# postomatMainBoard_2021-04-18_15-55-46.net
KiCad netlist of a schematic drawn in EasyEDA
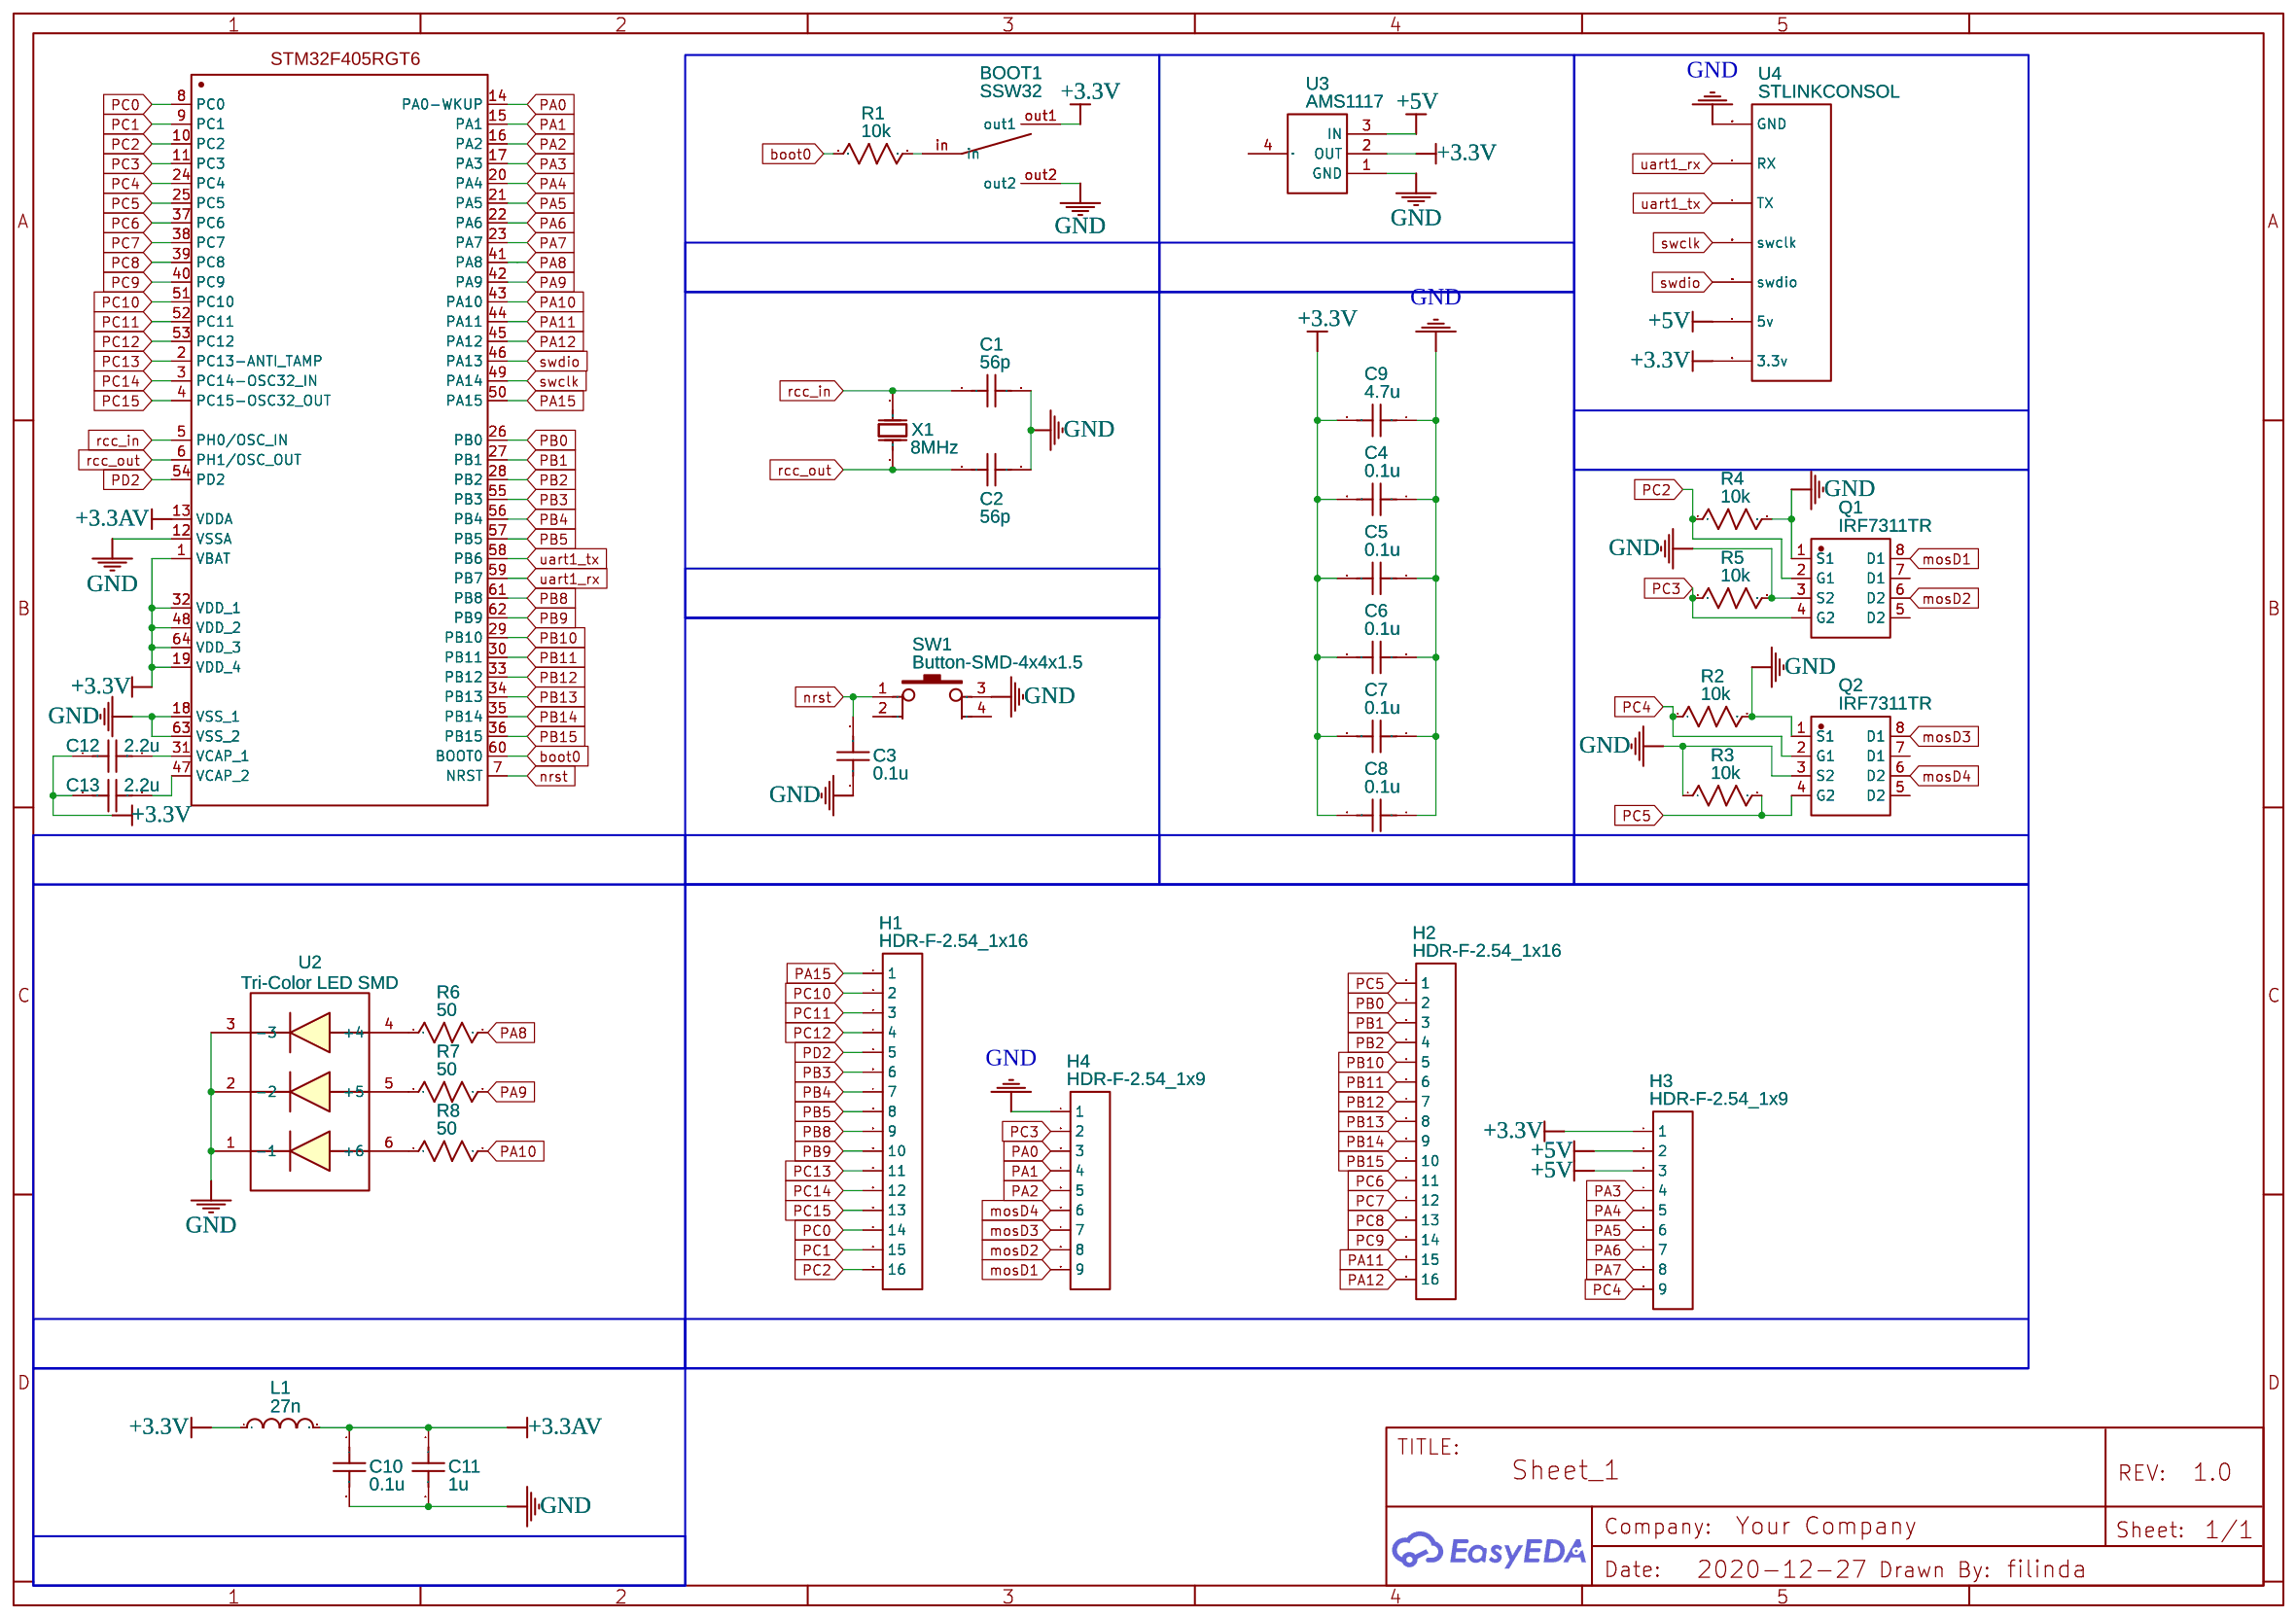
[diagram p0: schematic sheet]

(export (version "E")
  (design (tool "Eeschema 10.0.6"))
  (components
    (comp (ref "BOOT1") (value "SSW32") (libsource (lib "") (part "SSW32")))
    (comp (ref "C1") (value "56p") (libsource (lib "") (part "C_0805_US")))
    (comp (ref "C2") (value "56p") (libsource (lib "") (part "C_0805_US")))
    (comp (ref "C3") (value "0.1u") (libsource (lib "") (part "C_0603_US_3")))
    (comp (ref "C4") (value "0.1u") (libsource (lib "") (part "C_0603_US_1")))
    (comp (ref "C5") (value "0.1u") (libsource (lib "") (part "C_0603_US_1")))
    (comp (ref "C6") (value "0.1u") (libsource (lib "") (part "C_0603_US_1")))
    (comp (ref "C7") (value "0.1u") (libsource (lib "") (part "C_0603_US_1")))
    (comp (ref "C8") (value "0.1u") (libsource (lib "") (part "C_0603_US_1")))
    (comp (ref "C9") (value "4.7u") (libsource (lib "") (part "C_0603_US_1")))
    (comp (ref "C10") (value "0.1u") (libsource (lib "") (part "C_0603_US_2")))
    (comp (ref "C11") (value "1u") (libsource (lib "") (part "C_0603_US_2")))
    (comp (ref "C12") (value "2.2u") (libsource (lib "") (part "C_0603_US")))
    (comp (ref "C13") (value "2.2u") (libsource (lib "") (part "C_0603_US")))
    (comp (ref "H1")
      (value "HDR-F-2.54_1x16")
      (fields (field (name "BOM_Supplier Part") "C66987"))
      (libsource (lib "") (part "HDR-F-2.54_1x16"))
    )
    (comp (ref "H2")
      (value "HDR-F-2.54_1x16")
      (fields (field (name "BOM_Supplier Part") "C66987"))
      (libsource (lib "") (part "HDR-F-2.54_1x16"))
    )
    (comp (ref "H3")
      (value "HDR-F-2.54_1x9")
      (fields (field (name "BOM_Supplier Part") "C124417"))
      (libsource (lib "") (part "HDR-F-2.54_1x9"))
    )
    (comp (ref "H4")
      (value "HDR-F-2.54_1x9")
      (fields (field (name "BOM_Supplier Part") "C124417"))
      (libsource (lib "") (part "HDR-F-2.54_1x9"))
    )
    (comp (ref "L1") (value "27n") (libsource (lib "") (part "L0805_US")))
    (comp (ref "Q1")
      (value "IRF7311TR")
      (fields (field (name "BOM_Supplier Part") "C693288"))
      (libsource (lib "") (part "IRF7311TR"))
    )
    (comp (ref "Q2")
      (value "IRF7311TR")
      (fields (field (name "BOM_Supplier Part") "C693288"))
      (libsource (lib "") (part "IRF7311TR"))
    )
    (comp (ref "R1") (value "10k") (libsource (lib "") (part "R_1206_US")))
    (comp (ref "R2") (value "10k") (libsource (lib "") (part "R_1206_US")))
    (comp (ref "R3") (value "10k") (libsource (lib "") (part "R_1206_US")))
    (comp (ref "R4") (value "10k") (libsource (lib "") (part "R_1206_US")))
    (comp (ref "R5") (value "10k") (libsource (lib "") (part "R_1206_US")))
    (comp (ref "R6") (value "50") (libsource (lib "") (part "R_1206_US")))
    (comp (ref "R7") (value "50") (libsource (lib "") (part "R_1206_US")))
    (comp (ref "R8") (value "50") (libsource (lib "") (part "R_1206_US")))
    (comp (ref "SW1")
      (value "Button-SMD-4x4x1.5")
      (fields
        (field (name "BOM_Manufacturer Part") "4*4*1.5Copper head,260G, 0.25mm,")
        (field (name "BOM_Supplier Part") "C71830")
      )
      (libsource (lib "") (part "Button-SMD-4x4x1.5"))
    )
    (comp (ref "U1") (value "STM32F405RGT6") (libsource (lib "") (part "STM32F405RGT6")))
    (comp (ref "U2")
      (value "Tri-Color LED SMD")
      (fields
        (field (name "BOM_Manufacturer Part") "TO-5050BC-MRPBFGF")
        (field (name "BOM_Supplier Part") "A-4680")
      )
      (libsource (lib "") (part "Tri-Color LED SMD"))
    )
    (comp (ref "U3") (value "AMS1117") (libsource (lib "") (part "AMS1117")))
    (comp (ref "U4") (value "STLINKCONSOL") (libsource (lib "") (part "STLINKCONSOL")))
    (comp (ref "X1")
      (value "8MHz")
      (fields
        (field (name "BOM_Manufacturer Part") "HC-49SM8MHz20pF30ppm")
        (field (name "BOM_Supplier Part") "C107426")
      )
      (libsource (lib "") (part "HC-49SM8MHZ20PF30PPM"))
    )
  )
  (nets
    (net (code "1") (name "+3.3AV") (class "Default")
      (node (ref "C10") (pin "1") (pinfunction "1_1") (pintype "unspecified"))
      (node (ref "C11") (pin "1") (pinfunction "1_1") (pintype "unspecified"))
      (node (ref "L1") (pin "2") (pinfunction "2_2") (pintype "unspecified"))
      (node (ref "U1") (pin "13") (pinfunction "VDDA_13") (pintype "unspecified"))
    )
    (net (code "2") (name "+3.3V") (class "Default")
      (node (ref "BOOT1") (pin "out1") (pinfunction "out1_out1") (pintype "unspecified"))
      (node (ref "C12") (pin "1") (pinfunction "1_1") (pintype "unspecified"))
      (node (ref "C13") (pin "1") (pinfunction "1_1") (pintype "unspecified"))
      (node (ref "C4") (pin "2") (pinfunction "2_2") (pintype "unspecified"))
      (node (ref "C5") (pin "2") (pinfunction "2_2") (pintype "unspecified"))
      (node (ref "C6") (pin "2") (pinfunction "2_2") (pintype "unspecified"))
      (node (ref "C7") (pin "2") (pinfunction "2_2") (pintype "unspecified"))
      (node (ref "C8") (pin "2") (pinfunction "2_2") (pintype "unspecified"))
      (node (ref "C9") (pin "2") (pinfunction "2_2") (pintype "unspecified"))
      (node (ref "H3") (pin "1") (pinfunction "1_1") (pintype "unspecified"))
      (node (ref "L1") (pin "1") (pinfunction "1_1") (pintype "unspecified"))
      (node (ref "U1") (pin "1") (pinfunction "VBAT_1") (pintype "unspecified"))
      (node (ref "U1") (pin "19") (pinfunction "VDD_4_19") (pintype "unspecified"))
      (node (ref "U1") (pin "32") (pinfunction "VDD_1_32") (pintype "unspecified"))
      (node (ref "U1") (pin "48") (pinfunction "VDD_2_48") (pintype "unspecified"))
      (node (ref "U1") (pin "64") (pinfunction "VDD_3_64") (pintype "unspecified"))
      (node (ref "U3") (pin "2") (pinfunction "OUT_2") (pintype "unspecified"))
      (node (ref "U4") (pin "3.3v") (pinfunction "3.3v_3.3v") (pintype "unspecified"))
    )
    (net (code "3") (name "+5V") (class "Default")
      (node (ref "H3") (pin "2") (pinfunction "2_2") (pintype "unspecified"))
      (node (ref "H3") (pin "3") (pinfunction "3_3") (pintype "unspecified"))
      (node (ref "U3") (pin "3") (pinfunction "IN_3") (pintype "unspecified"))
      (node (ref "U4") (pin "5v") (pinfunction "5v_5v") (pintype "unspecified"))
    )
    (net (code "4") (name "GND") (class "Default")
      (node (ref "BOOT1") (pin "out2") (pinfunction "out2_out2") (pintype "unspecified"))
      (node (ref "C1") (pin "2") (pinfunction "2_2") (pintype "unspecified"))
      (node (ref "C10") (pin "2") (pinfunction "2_2") (pintype "unspecified"))
      (node (ref "C11") (pin "2") (pinfunction "2_2") (pintype "unspecified"))
      (node (ref "C2") (pin "2") (pinfunction "2_2") (pintype "unspecified"))
      (node (ref "C3") (pin "1") (pinfunction "1_1") (pintype "unspecified"))
      (node (ref "C4") (pin "1") (pinfunction "1_1") (pintype "unspecified"))
      (node (ref "C5") (pin "1") (pinfunction "1_1") (pintype "unspecified"))
      (node (ref "C6") (pin "1") (pinfunction "1_1") (pintype "unspecified"))
      (node (ref "C7") (pin "1") (pinfunction "1_1") (pintype "unspecified"))
      (node (ref "C8") (pin "1") (pinfunction "1_1") (pintype "unspecified"))
      (node (ref "C9") (pin "1") (pinfunction "1_1") (pintype "unspecified"))
      (node (ref "H4") (pin "1") (pinfunction "1_1") (pintype "unspecified"))
      (node (ref "Q1") (pin "1") (pinfunction "S1_1") (pintype "unspecified"))
      (node (ref "Q1") (pin "3") (pinfunction "S2_3") (pintype "unspecified"))
      (node (ref "Q2") (pin "1") (pinfunction "S1_1") (pintype "unspecified"))
      (node (ref "Q2") (pin "3") (pinfunction "S2_3") (pintype "unspecified"))
      (node (ref "R2") (pin "2") (pinfunction "2_2") (pintype "unspecified"))
      (node (ref "R3") (pin "1") (pinfunction "1_1") (pintype "unspecified"))
      (node (ref "R4") (pin "2") (pinfunction "2_2") (pintype "unspecified"))
      (node (ref "R5") (pin "2") (pinfunction "2_2") (pintype "unspecified"))
      (node (ref "SW1") (pin "3") (pinfunction "3_3") (pintype "input"))
      (node (ref "U1") (pin "12") (pinfunction "VSSA_12") (pintype "unspecified"))
      (node (ref "U1") (pin "18") (pinfunction "VSS_1_18") (pintype "unspecified"))
      (node (ref "U1") (pin "63") (pinfunction "VSS_2_63") (pintype "unspecified"))
      (node (ref "U2") (pin "1") (pinfunction "-1_1") (pintype "unspecified"))
      (node (ref "U2") (pin "2") (pinfunction "-2_2") (pintype "unspecified"))
      (node (ref "U2") (pin "3") (pinfunction "-3_3") (pintype "unspecified"))
      (node (ref "U3") (pin "1") (pinfunction "GND_1") (pintype "unspecified"))
      (node (ref "U4") (pin "GND") (pinfunction "GND_GND") (pintype "unspecified"))
    )
    (net (code "5") (name "Net-(BOOT1-Padin)") (class "Default")
      (node (ref "BOOT1") (pin "in") (pinfunction "in_in") (pintype "unspecified"))
      (node (ref "R1") (pin "2") (pinfunction "2_2") (pintype "unspecified"))
    )
    (net (code "6") (name "Net-(U1-VCAP_1)") (class "Default")
      (node (ref "C12") (pin "2") (pinfunction "2_2") (pintype "unspecified"))
      (node (ref "U1") (pin "31") (pinfunction "VCAP_1_31") (pintype "unspecified"))
    )
    (net (code "7") (name "Net-(U1-VCAP_2)") (class "Default")
      (node (ref "C13") (pin "2") (pinfunction "2_2") (pintype "unspecified"))
      (node (ref "U1") (pin "47") (pinfunction "VCAP_2_47") (pintype "unspecified"))
    )
    (net (code "8") (name "Net-(U2-+4)") (class "Default")
      (node (ref "R6") (pin "1") (pinfunction "1_1") (pintype "unspecified"))
      (node (ref "U2") (pin "4") (pinfunction "+4_4") (pintype "unspecified"))
    )
    (net (code "9") (name "Net-(U2-+5)") (class "Default")
      (node (ref "R7") (pin "1") (pinfunction "1_1") (pintype "unspecified"))
      (node (ref "U2") (pin "5") (pinfunction "+5_5") (pintype "unspecified"))
    )
    (net (code "10") (name "Net-(U2-+6)") (class "Default")
      (node (ref "R8") (pin "1") (pinfunction "1_1") (pintype "unspecified"))
      (node (ref "U2") (pin "6") (pinfunction "+6_6") (pintype "unspecified"))
    )
    (net (code "11") (name "PA0") (class "Default")
      (node (ref "H4") (pin "3") (pinfunction "3_3") (pintype "unspecified"))
      (node (ref "U1") (pin "14") (pinfunction "PA0-WKUP_14") (pintype "unspecified"))
    )
    (net (code "12") (name "PA1") (class "Default")
      (node (ref "H4") (pin "4") (pinfunction "4_4") (pintype "unspecified"))
      (node (ref "U1") (pin "15") (pinfunction "PA1_15") (pintype "unspecified"))
    )
    (net (code "13") (name "PA2") (class "Default")
      (node (ref "H4") (pin "5") (pinfunction "5_5") (pintype "unspecified"))
      (node (ref "U1") (pin "16") (pinfunction "PA2_16") (pintype "unspecified"))
    )
    (net (code "14") (name "PA3") (class "Default")
      (node (ref "H3") (pin "4") (pinfunction "4_4") (pintype "unspecified"))
      (node (ref "U1") (pin "17") (pinfunction "PA3_17") (pintype "unspecified"))
    )
    (net (code "15") (name "PA4") (class "Default")
      (node (ref "H3") (pin "5") (pinfunction "5_5") (pintype "unspecified"))
      (node (ref "U1") (pin "20") (pinfunction "PA4_20") (pintype "unspecified"))
    )
    (net (code "16") (name "PA5") (class "Default")
      (node (ref "H3") (pin "6") (pinfunction "6_6") (pintype "unspecified"))
      (node (ref "U1") (pin "21") (pinfunction "PA5_21") (pintype "unspecified"))
    )
    (net (code "17") (name "PA6") (class "Default")
      (node (ref "H3") (pin "7") (pinfunction "7_7") (pintype "unspecified"))
      (node (ref "U1") (pin "22") (pinfunction "PA6_22") (pintype "unspecified"))
    )
    (net (code "18") (name "PA7") (class "Default")
      (node (ref "H3") (pin "8") (pinfunction "8_8") (pintype "unspecified"))
      (node (ref "U1") (pin "23") (pinfunction "PA7_23") (pintype "unspecified"))
    )
    (net (code "19") (name "PA8") (class "Default")
      (node (ref "R6") (pin "2") (pinfunction "2_2") (pintype "unspecified"))
      (node (ref "U1") (pin "41") (pinfunction "PA8_41") (pintype "unspecified"))
    )
    (net (code "20") (name "PA9") (class "Default")
      (node (ref "R7") (pin "2") (pinfunction "2_2") (pintype "unspecified"))
      (node (ref "U1") (pin "42") (pinfunction "PA9_42") (pintype "unspecified"))
    )
    (net (code "21") (name "PA10") (class "Default")
      (node (ref "R8") (pin "2") (pinfunction "2_2") (pintype "unspecified"))
      (node (ref "U1") (pin "43") (pinfunction "PA10_43") (pintype "unspecified"))
    )
    (net (code "22") (name "PA11") (class "Default")
      (node (ref "H2") (pin "15") (pinfunction "15_15") (pintype "unspecified"))
      (node (ref "U1") (pin "44") (pinfunction "PA11_44") (pintype "unspecified"))
    )
    (net (code "23") (name "PA12") (class "Default")
      (node (ref "H2") (pin "16") (pinfunction "16_16") (pintype "unspecified"))
      (node (ref "U1") (pin "45") (pinfunction "PA12_45") (pintype "unspecified"))
    )
    (net (code "24") (name "PA15") (class "Default")
      (node (ref "H1") (pin "1") (pinfunction "1_1") (pintype "unspecified"))
      (node (ref "U1") (pin "50") (pinfunction "PA15_50") (pintype "unspecified"))
    )
    (net (code "25") (name "PB0") (class "Default")
      (node (ref "H2") (pin "2") (pinfunction "2_2") (pintype "unspecified"))
      (node (ref "U1") (pin "26") (pinfunction "PB0_26") (pintype "unspecified"))
    )
    (net (code "26") (name "PB1") (class "Default")
      (node (ref "H2") (pin "3") (pinfunction "3_3") (pintype "unspecified"))
      (node (ref "U1") (pin "27") (pinfunction "PB1_27") (pintype "unspecified"))
    )
    (net (code "27") (name "PB2") (class "Default")
      (node (ref "H2") (pin "4") (pinfunction "4_4") (pintype "unspecified"))
      (node (ref "U1") (pin "28") (pinfunction "PB2_28") (pintype "unspecified"))
    )
    (net (code "28") (name "PB3") (class "Default")
      (node (ref "H1") (pin "6") (pinfunction "6_6") (pintype "unspecified"))
      (node (ref "U1") (pin "55") (pinfunction "PB3_55") (pintype "unspecified"))
    )
    (net (code "29") (name "PB4") (class "Default")
      (node (ref "H1") (pin "7") (pinfunction "7_7") (pintype "unspecified"))
      (node (ref "U1") (pin "56") (pinfunction "PB4_56") (pintype "unspecified"))
    )
    (net (code "30") (name "PB5") (class "Default")
      (node (ref "H1") (pin "8") (pinfunction "8_8") (pintype "unspecified"))
      (node (ref "U1") (pin "57") (pinfunction "PB5_57") (pintype "unspecified"))
    )
    (net (code "31") (name "PB8") (class "Default")
      (node (ref "H1") (pin "9") (pinfunction "9_9") (pintype "unspecified"))
      (node (ref "U1") (pin "61") (pinfunction "PB8_61") (pintype "unspecified"))
    )
    (net (code "32") (name "PB9") (class "Default")
      (node (ref "H1") (pin "10") (pinfunction "10_10") (pintype "unspecified"))
      (node (ref "U1") (pin "62") (pinfunction "PB9_62") (pintype "unspecified"))
    )
    (net (code "33") (name "PB10") (class "Default")
      (node (ref "H2") (pin "5") (pinfunction "5_5") (pintype "unspecified"))
      (node (ref "U1") (pin "29") (pinfunction "PB10_29") (pintype "unspecified"))
    )
    (net (code "34") (name "PB11") (class "Default")
      (node (ref "H2") (pin "6") (pinfunction "6_6") (pintype "unspecified"))
      (node (ref "U1") (pin "30") (pinfunction "PB11_30") (pintype "unspecified"))
    )
    (net (code "35") (name "PB12") (class "Default")
      (node (ref "H2") (pin "7") (pinfunction "7_7") (pintype "unspecified"))
      (node (ref "U1") (pin "33") (pinfunction "PB12_33") (pintype "unspecified"))
    )
    (net (code "36") (name "PB13") (class "Default")
      (node (ref "H2") (pin "8") (pinfunction "8_8") (pintype "unspecified"))
      (node (ref "U1") (pin "34") (pinfunction "PB13_34") (pintype "unspecified"))
    )
    (net (code "37") (name "PB14") (class "Default")
      (node (ref "H2") (pin "9") (pinfunction "9_9") (pintype "unspecified"))
      (node (ref "U1") (pin "35") (pinfunction "PB14_35") (pintype "unspecified"))
    )
    (net (code "38") (name "PB15") (class "Default")
      (node (ref "H2") (pin "10") (pinfunction "10_10") (pintype "unspecified"))
      (node (ref "U1") (pin "36") (pinfunction "PB15_36") (pintype "unspecified"))
    )
    (net (code "39") (name "PC0") (class "Default")
      (node (ref "H1") (pin "14") (pinfunction "14_14") (pintype "unspecified"))
      (node (ref "U1") (pin "8") (pinfunction "PC0_8") (pintype "unspecified"))
    )
    (net (code "40") (name "PC1") (class "Default")
      (node (ref "H1") (pin "15") (pinfunction "15_15") (pintype "unspecified"))
      (node (ref "U1") (pin "9") (pinfunction "PC1_9") (pintype "unspecified"))
    )
    (net (code "41") (name "PC2") (class "Default")
      (node (ref "H1") (pin "16") (pinfunction "16_16") (pintype "unspecified"))
      (node (ref "Q1") (pin "2") (pinfunction "G1_2") (pintype "unspecified"))
      (node (ref "R4") (pin "1") (pinfunction "1_1") (pintype "unspecified"))
      (node (ref "U1") (pin "10") (pinfunction "PC2_10") (pintype "unspecified"))
    )
    (net (code "42") (name "PC3") (class "Default")
      (node (ref "H4") (pin "2") (pinfunction "2_2") (pintype "unspecified"))
      (node (ref "Q1") (pin "4") (pinfunction "G2_4") (pintype "unspecified"))
      (node (ref "R5") (pin "1") (pinfunction "1_1") (pintype "unspecified"))
      (node (ref "U1") (pin "11") (pinfunction "PC3_11") (pintype "unspecified"))
    )
    (net (code "43") (name "PC4") (class "Default")
      (node (ref "H3") (pin "9") (pinfunction "9_9") (pintype "unspecified"))
      (node (ref "Q2") (pin "2") (pinfunction "G1_2") (pintype "unspecified"))
      (node (ref "R2") (pin "1") (pinfunction "1_1") (pintype "unspecified"))
      (node (ref "U1") (pin "24") (pinfunction "PC4_24") (pintype "unspecified"))
    )
    (net (code "44") (name "PC5") (class "Default")
      (node (ref "H2") (pin "1") (pinfunction "1_1") (pintype "unspecified"))
      (node (ref "Q2") (pin "4") (pinfunction "G2_4") (pintype "unspecified"))
      (node (ref "R3") (pin "2") (pinfunction "2_2") (pintype "unspecified"))
      (node (ref "U1") (pin "25") (pinfunction "PC5_25") (pintype "unspecified"))
    )
    (net (code "45") (name "PC6") (class "Default")
      (node (ref "H2") (pin "11") (pinfunction "11_11") (pintype "unspecified"))
      (node (ref "U1") (pin "37") (pinfunction "PC6_37") (pintype "unspecified"))
    )
    (net (code "46") (name "PC7") (class "Default")
      (node (ref "H2") (pin "12") (pinfunction "12_12") (pintype "unspecified"))
      (node (ref "U1") (pin "38") (pinfunction "PC7_38") (pintype "unspecified"))
    )
    (net (code "47") (name "PC8") (class "Default")
      (node (ref "H2") (pin "13") (pinfunction "13_13") (pintype "unspecified"))
      (node (ref "U1") (pin "39") (pinfunction "PC8_39") (pintype "unspecified"))
    )
    (net (code "48") (name "PC9") (class "Default")
      (node (ref "H2") (pin "14") (pinfunction "14_14") (pintype "unspecified"))
      (node (ref "U1") (pin "40") (pinfunction "PC9_40") (pintype "unspecified"))
    )
    (net (code "49") (name "PC10") (class "Default")
      (node (ref "H1") (pin "2") (pinfunction "2_2") (pintype "unspecified"))
      (node (ref "U1") (pin "51") (pinfunction "PC10_51") (pintype "unspecified"))
    )
    (net (code "50") (name "PC11") (class "Default")
      (node (ref "H1") (pin "3") (pinfunction "3_3") (pintype "unspecified"))
      (node (ref "U1") (pin "52") (pinfunction "PC11_52") (pintype "unspecified"))
    )
    (net (code "51") (name "PC12") (class "Default")
      (node (ref "H1") (pin "4") (pinfunction "4_4") (pintype "unspecified"))
      (node (ref "U1") (pin "53") (pinfunction "PC12_53") (pintype "unspecified"))
    )
    (net (code "52") (name "PC13") (class "Default")
      (node (ref "H1") (pin "11") (pinfunction "11_11") (pintype "unspecified"))
      (node (ref "U1") (pin "2") (pinfunction "PC13-ANTI_TAMP_2") (pintype "unspecified"))
    )
    (net (code "53") (name "PC14") (class "Default")
      (node (ref "H1") (pin "12") (pinfunction "12_12") (pintype "unspecified"))
      (node (ref "U1") (pin "3") (pinfunction "PC14-OSC32_IN_3") (pintype "unspecified"))
    )
    (net (code "54") (name "PC15") (class "Default")
      (node (ref "H1") (pin "13") (pinfunction "13_13") (pintype "unspecified"))
      (node (ref "U1") (pin "4") (pinfunction "PC15-OSC32_OUT_4") (pintype "unspecified"))
    )
    (net (code "55") (name "PD2") (class "Default")
      (node (ref "H1") (pin "5") (pinfunction "5_5") (pintype "unspecified"))
      (node (ref "U1") (pin "54") (pinfunction "PD2_54") (pintype "unspecified"))
    )
    (net (code "56") (name "boot0") (class "Default")
      (node (ref "R1") (pin "1") (pinfunction "1_1") (pintype "unspecified"))
      (node (ref "U1") (pin "60") (pinfunction "BOOT0_60") (pintype "unspecified"))
    )
    (net (code "57") (name "mosD1") (class "Default")
      (node (ref "H4") (pin "9") (pinfunction "9_9") (pintype "unspecified"))
      (node (ref "Q1") (pin "8") (pinfunction "D1_8") (pintype "unspecified"))
    )
    (net (code "58") (name "mosD2") (class "Default")
      (node (ref "H4") (pin "8") (pinfunction "8_8") (pintype "unspecified"))
      (node (ref "Q1") (pin "6") (pinfunction "D2_6") (pintype "unspecified"))
    )
    (net (code "59") (name "mosD3") (class "Default")
      (node (ref "H4") (pin "7") (pinfunction "7_7") (pintype "unspecified"))
      (node (ref "Q2") (pin "8") (pinfunction "D1_8") (pintype "unspecified"))
    )
    (net (code "60") (name "mosD4") (class "Default")
      (node (ref "H4") (pin "6") (pinfunction "6_6") (pintype "unspecified"))
      (node (ref "Q2") (pin "6") (pinfunction "D2_6") (pintype "unspecified"))
    )
    (net (code "61") (name "nrst") (class "Default")
      (node (ref "C3") (pin "2") (pinfunction "2_2") (pintype "unspecified"))
      (node (ref "SW1") (pin "1") (pinfunction "1_1") (pintype "input"))
      (node (ref "U1") (pin "7") (pinfunction "NRST_7") (pintype "unspecified"))
    )
    (net (code "62") (name "rcc_in") (class "Default")
      (node (ref "C1") (pin "1") (pinfunction "1_1") (pintype "unspecified"))
      (node (ref "U1") (pin "5") (pinfunction "PH0/OSC_IN_5") (pintype "unspecified"))
      (node (ref "X1") (pin "1") (pinfunction "OSC1_1") (pintype "input"))
    )
    (net (code "63") (name "rcc_out") (class "Default")
      (node (ref "C2") (pin "1") (pinfunction "1_1") (pintype "unspecified"))
      (node (ref "U1") (pin "6") (pinfunction "PH1/OSC_OUT_6") (pintype "unspecified"))
      (node (ref "X1") (pin "2") (pinfunction "OSC2_2") (pintype "input"))
    )
    (net (code "64") (name "swclk") (class "Default")
      (node (ref "U1") (pin "49") (pinfunction "PA14_49") (pintype "unspecified"))
      (node (ref "U4") (pin "swclk") (pinfunction "swclk_swclk") (pintype "unspecified"))
    )
    (net (code "65") (name "swdio") (class "Default")
      (node (ref "U1") (pin "46") (pinfunction "PA13_46") (pintype "unspecified"))
      (node (ref "U4") (pin "swdio") (pinfunction "swdio_swdio") (pintype "unspecified"))
    )
    (net (code "66") (name "uart1_rx") (class "Default")
      (node (ref "U1") (pin "59") (pinfunction "PB7_59") (pintype "unspecified"))
      (node (ref "U4") (pin "RX") (pinfunction "RX_RX") (pintype "unspecified"))
    )
    (net (code "67") (name "uart1_tx") (class "Default")
      (node (ref "U1") (pin "58") (pinfunction "PB6_58") (pintype "unspecified"))
      (node (ref "U4") (pin "TX") (pinfunction "TX_TX") (pintype "unspecified"))
    )
    (net (code "68") (name "unconnected-(Q1-D1-Pad7)") (class "Default")
      (node (ref "Q1") (pin "7") (pinfunction "D1_7") (pintype "unspecified"))
    )
    (net (code "69") (name "unconnected-(Q1-D2-Pad5)") (class "Default")
      (node (ref "Q1") (pin "5") (pinfunction "D2_5") (pintype "unspecified"))
    )
    (net (code "70") (name "unconnected-(Q2-D1-Pad7)") (class "Default")
      (node (ref "Q2") (pin "7") (pinfunction "D1_7") (pintype "unspecified"))
    )
    (net (code "71") (name "unconnected-(Q2-D2-Pad5)") (class "Default")
      (node (ref "Q2") (pin "5") (pinfunction "D2_5") (pintype "unspecified"))
    )
    (net (code "72") (name "unconnected-(SW1-Pad2)") (class "Default")
      (node (ref "SW1") (pin "2") (pinfunction "2_2") (pintype "input"))
    )
    (net (code "73") (name "unconnected-(SW1-Pad4)") (class "Default")
      (node (ref "SW1") (pin "4") (pinfunction "4_4") (pintype "input"))
    )
    (net (code "74") (name "unconnected-(U3-GND-Pad4)") (class "Default")
      (node (ref "U3") (pin "4") (pinfunction "GND_4") (pintype "unspecified"))
    )
  )
)
